# Main_MCU.net
KiCad netlist of a schematic drawn in Altium Designer
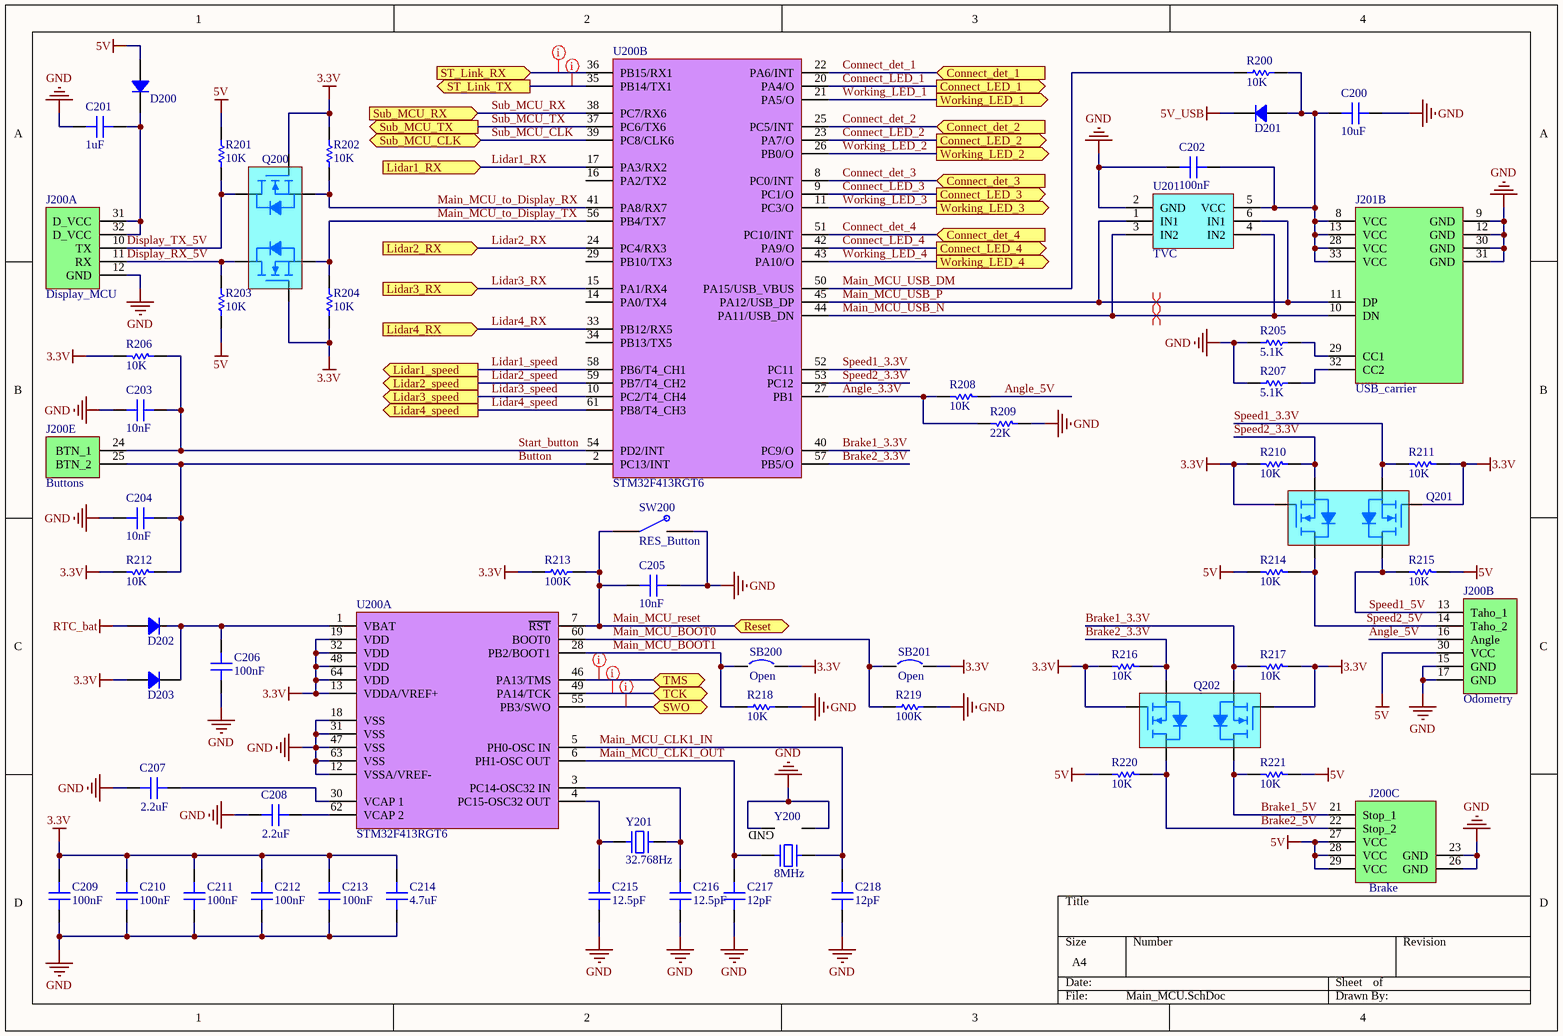
[diagram p0: Main_MCU.SchDoc]

(export (version "E")
  (design (tool "Eeschema 10.0.6"))
  (components
    (comp (ref "C200")
      (value "10uF")
      (footprint "CAP 0603")
      (description "SMT Capacitor")
      (libsource (lib "Schlib1") (part "Capacitor"))
    )
    (comp (ref "C201")
      (value "1uF")
      (footprint "CAP 0603")
      (description "SMT Capacitor")
      (libsource (lib "Schlib1") (part "Capacitor"))
    )
    (comp (ref "C202")
      (value "100nF")
      (footprint "CAP 0603")
      (description "SMT Capacitor")
      (libsource (lib "Schlib1") (part "Capacitor"))
    )
    (comp (ref "C203")
      (value "10nF")
      (footprint "CAP 0603")
      (description "SMT Capacitor")
      (libsource (lib "Schlib1") (part "Capacitor"))
    )
    (comp (ref "C204")
      (value "10nF")
      (footprint "CAP 0603")
      (description "SMT Capacitor")
      (libsource (lib "Schlib1") (part "Capacitor"))
    )
    (comp (ref "C205")
      (value "10nF")
      (footprint "CAP 0603")
      (description "SMT Capacitor")
      (libsource (lib "Schlib1") (part "Capacitor"))
    )
    (comp (ref "C206")
      (value "100nF")
      (footprint "CAP 0603")
      (description "SMT Capacitor")
      (libsource (lib "Schlib1") (part "Capacitor"))
    )
    (comp (ref "C207")
      (value "2.2uF")
      (footprint "CAP 0603")
      (description "SMT Capacitor")
      (libsource (lib "Schlib1") (part "Capacitor"))
    )
    (comp (ref "C208")
      (value "2.2uF")
      (footprint "CAP 0603")
      (description "SMT Capacitor")
      (libsource (lib "Schlib1") (part "Capacitor"))
    )
    (comp (ref "C209")
      (value "100nF")
      (footprint "CAP 0603")
      (description "SMT Capacitor")
      (libsource (lib "Schlib1") (part "Capacitor"))
    )
    (comp (ref "C210")
      (value "100nF")
      (footprint "CAP 0603")
      (description "SMT Capacitor")
      (libsource (lib "Schlib1") (part "Capacitor"))
    )
    (comp (ref "C211")
      (value "100nF")
      (footprint "CAP 0603")
      (description "SMT Capacitor")
      (libsource (lib "Schlib1") (part "Capacitor"))
    )
    (comp (ref "C212")
      (value "100nF")
      (footprint "CAP 0603")
      (description "SMT Capacitor")
      (libsource (lib "Schlib1") (part "Capacitor"))
    )
    (comp (ref "C213")
      (value "100nF")
      (footprint "CAP 0603")
      (description "SMT Capacitor")
      (libsource (lib "Schlib1") (part "Capacitor"))
    )
    (comp (ref "C214")
      (value "4.7uF")
      (footprint "CAP 1206")
      (description "SMT Capacitor")
      (libsource (lib "Schlib1") (part "Capacitor"))
    )
    (comp (ref "C215")
      (value "12.5pF")
      (footprint "CAP 0603")
      (description "SMT Capacitor")
      (libsource (lib "Schlib1") (part "Capacitor"))
    )
    (comp (ref "C216")
      (value "12.5pF")
      (footprint "CAP 0603")
      (description "SMT Capacitor")
      (libsource (lib "Schlib1") (part "Capacitor"))
    )
    (comp (ref "C217")
      (value "12pF")
      (footprint "CAP 0603")
      (description "SMT Capacitor")
      (libsource (lib "Schlib1") (part "Capacitor"))
    )
    (comp (ref "C218")
      (value "12pF")
      (footprint "CAP 0603")
      (description "SMT Capacitor")
      (libsource (lib "Schlib1") (part "Capacitor"))
    )
    (comp (ref "D200")
      (value "~")
      (footprint "Bourns DO214AC SMA - duplicate")
      (description "Rectifier Diode")
      (libsource (lib "Schlib1") (part "Diode"))
    )
    (comp (ref "D201")
      (value "~")
      (footprint "Bourns DO214AC SMA - duplicate")
      (description "Rectifier Diode")
      (libsource (lib "Schlib1") (part "Diode"))
    )
    (comp (ref "D202")
      (value "~")
      (footprint "SOD323HP")
      (description "Rectifier Diode")
      (libsource (lib "Schlib1") (part "Diode"))
    )
    (comp (ref "D203")
      (value "~")
      (footprint "SOD323HP")
      (description "Rectifier Diode")
      (libsource (lib "Schlib1") (part "Diode"))
    )
    (comp (ref "J200")
      (value "Display_MCU")
      (footprint "2167010409")
      (libsource (lib "Schlib1") (part "AUX_carrier"))
    )
    (comp (ref "J201")
      (value "USB_carrier")
      (footprint "2167010409")
      (libsource (lib "Schlib1") (part "USB_carrier"))
    )
    (comp (ref "Q200")
      (value "Double N mos")
      (footprint "TI SOT-563 DRL")
      (libsource (lib "") (part "Double N mos_1"))
    )
    (comp (ref "Q201")
      (value "Double N mos")
      (footprint "TI SOT-563 DRL")
      (libsource (lib "Schlib1") (part "Double N mos"))
    )
    (comp (ref "Q202")
      (value "Double N mos")
      (footprint "TI SOT-563 DRL")
      (libsource (lib "Schlib1") (part "Double N mos"))
    )
    (comp (ref "R200")
      (value "10K")
      (footprint "RES 0603")
      (description "Resistor")
      (fields (field (name "PUBLISHER") "Altium Limited"))
      (libsource (lib "Schlib1") (part "Res"))
    )
    (comp (ref "R201")
      (value "10K")
      (footprint "RES 0603")
      (description "Resistor")
      (fields (field (name "PUBLISHER") "Altium Limited"))
      (libsource (lib "Schlib1") (part "Res"))
    )
    (comp (ref "R202")
      (value "10K")
      (footprint "RES 0603")
      (description "Resistor")
      (fields (field (name "PUBLISHER") "Altium Limited"))
      (libsource (lib "Schlib1") (part "Res"))
    )
    (comp (ref "R203")
      (value "10K")
      (footprint "RES 0603")
      (description "Resistor")
      (fields (field (name "PUBLISHER") "Altium Limited"))
      (libsource (lib "Schlib1") (part "Res"))
    )
    (comp (ref "R204")
      (value "10K")
      (footprint "RES 0603")
      (description "Resistor")
      (fields (field (name "PUBLISHER") "Altium Limited"))
      (libsource (lib "Schlib1") (part "Res"))
    )
    (comp (ref "R205")
      (value "5.1K")
      (footprint "RES 0603")
      (description "Resistor")
      (fields (field (name "PUBLISHER") "Altium Limited"))
      (libsource (lib "Schlib1") (part "Res"))
    )
    (comp (ref "R206")
      (value "10K")
      (footprint "RES 0603")
      (description "Resistor")
      (fields (field (name "PUBLISHER") "Altium Limited"))
      (libsource (lib "Schlib1") (part "Res"))
    )
    (comp (ref "R207")
      (value "5.1K")
      (footprint "RES 0603")
      (description "Resistor")
      (fields (field (name "PUBLISHER") "Altium Limited"))
      (libsource (lib "Schlib1") (part "Res"))
    )
    (comp (ref "R208")
      (value "10K")
      (footprint "RES 0603")
      (description "Resistor")
      (fields (field (name "PUBLISHER") "Altium Limited"))
      (libsource (lib "Schlib1") (part "Res"))
    )
    (comp (ref "R209")
      (value "22K")
      (footprint "RES 0603")
      (description "Resistor")
      (fields (field (name "PUBLISHER") "Altium Limited"))
      (libsource (lib "Schlib1") (part "Res"))
    )
    (comp (ref "R210")
      (value "10K")
      (footprint "RES 0603")
      (description "Resistor")
      (fields (field (name "PUBLISHER") "Altium Limited"))
      (libsource (lib "Schlib1") (part "Res"))
    )
    (comp (ref "R211")
      (value "10K")
      (footprint "RES 0603")
      (description "Resistor")
      (fields (field (name "PUBLISHER") "Altium Limited"))
      (libsource (lib "Schlib1") (part "Res"))
    )
    (comp (ref "R212")
      (value "10K")
      (footprint "RES 0603")
      (description "Resistor")
      (fields (field (name "PUBLISHER") "Altium Limited"))
      (libsource (lib "Schlib1") (part "Res"))
    )
    (comp (ref "R213")
      (value "100K")
      (footprint "RES 0603")
      (description "Resistor")
      (fields (field (name "PUBLISHER") "Altium Limited"))
      (libsource (lib "Schlib1") (part "Res"))
    )
    (comp (ref "R214")
      (value "10K")
      (footprint "RES 0603")
      (description "Resistor")
      (fields (field (name "PUBLISHER") "Altium Limited"))
      (libsource (lib "Schlib1") (part "Res"))
    )
    (comp (ref "R215")
      (value "10K")
      (footprint "RES 0603")
      (description "Resistor")
      (fields (field (name "PUBLISHER") "Altium Limited"))
      (libsource (lib "Schlib1") (part "Res"))
    )
    (comp (ref "R216")
      (value "10K")
      (footprint "RES 0603")
      (description "Resistor")
      (fields (field (name "PUBLISHER") "Altium Limited"))
      (libsource (lib "Schlib1") (part "Res"))
    )
    (comp (ref "R217")
      (value "10K")
      (footprint "RES 0603")
      (description "Resistor")
      (fields (field (name "PUBLISHER") "Altium Limited"))
      (libsource (lib "Schlib1") (part "Res"))
    )
    (comp (ref "R218")
      (value "10K")
      (footprint "RES 0603")
      (description "Resistor")
      (fields (field (name "PUBLISHER") "Altium Limited"))
      (libsource (lib "Schlib1") (part "Res"))
    )
    (comp (ref "R219")
      (value "100K")
      (footprint "RES 0603")
      (description "Resistor")
      (fields (field (name "PUBLISHER") "Altium Limited"))
      (libsource (lib "Schlib1") (part "Res"))
    )
    (comp (ref "R220")
      (value "10K")
      (footprint "RES 0603")
      (description "Resistor")
      (fields (field (name "PUBLISHER") "Altium Limited"))
      (libsource (lib "Schlib1") (part "Res"))
    )
    (comp (ref "R221")
      (value "10K")
      (footprint "RES 0603")
      (description "Resistor")
      (fields (field (name "PUBLISHER") "Altium Limited"))
      (libsource (lib "Schlib1") (part "Res"))
    )
    (comp (ref "SB200")
      (value "Open")
      (footprint "SB_0603")
      (description "Circuit Breaker")
      (fields (field (name "PUBLISHER") "Altium Limited"))
      (libsource (lib "Schlib1") (part "Circuit Breaker"))
    )
    (comp (ref "SB201")
      (value "Open")
      (footprint "SB_0603")
      (description "Circuit Breaker")
      (fields (field (name "PUBLISHER") "Altium Limited"))
      (libsource (lib "Schlib1") (part "Circuit Breaker"))
    )
    (comp (ref "SW200")
      (value "RES_Button")
      (footprint "PTS636SM50JSMTRLFS")
      (libsource (lib "Schlib1") (part "RES_Button"))
    )
    (comp (ref "U200")
      (value "STM32F413RGT6")
      (footprint "QFP50P1200X1200X165-64N")
      (description "IC MCU 32BIT 1MB FLASH 64LQFP")
      (fields
        (field (name "MANUFACTURER") "STMicroelectronics")
        (field (name "OCTOPART") "https://octopart.com/stm32f413rgt6-stmicroelectronics-76512522")
      )
      (libsource (lib "Schlib1") (part "CMP-12105-000025-1"))
    )
    (comp (ref "U201")
      (value "TVC")
      (footprint "ECEN_1400:DIODES SOT-23-6 W6")
      (libsource (lib "Schlib1") (part "USB_TVC_protection"))
    )
    (comp (ref "Y200")
      (value "8MHz")
      (footprint "XTAL_ECS-80-10-33-CHN-TR3")
      (description "SMT Crystal")
      (libsource (lib "Schlib1") (part "Crystal 8Mhz"))
    )
    (comp (ref "Y201")
      (value "32.768Hz")
      (footprint "Crystal_32.768")
      (description "SMT Crystal")
      (libsource (lib "Schlib1") (part "Crystal_32.768Hz"))
    )
  )
  (nets
    (net (code "1") (name "/Angle_3.3V") (class "Default")
      (node (ref "R208") (pin "1") (pinfunction "1_1") (pintype "passive"))
      (node (ref "R209") (pin "1") (pinfunction "1_1") (pintype "passive"))
      (node (ref "U200") (pin "27") (pinfunction "PB1_27") (pintype "passive"))
    )
    (net (code "2") (name "/Angle_5V") (class "Default")
      (node (ref "J200") (pin "16") (pinfunction "Angle_16") (pintype "passive"))
      (node (ref "R208") (pin "2") (pinfunction "2_2") (pintype "passive"))
    )
    (net (code "3") (name "/Brake1_3.3V") (class "Default")
      (node (ref "Q202") (pin "5") (pinfunction "S1_5") (pintype "passive"))
      (node (ref "R217") (pin "1") (pinfunction "1_1") (pintype "passive"))
      (node (ref "U200") (pin "40") (pinfunction "PC9/O_40") (pintype "passive"))
    )
    (net (code "4") (name "/Brake1_5V") (class "Default")
      (node (ref "J200") (pin "21") (pinfunction "Stop_1_21") (pintype "passive"))
      (node (ref "Q202") (pin "3") (pinfunction "D1_3") (pintype "passive"))
      (node (ref "R221") (pin "1") (pinfunction "1_1") (pintype "passive"))
    )
    (net (code "5") (name "/Brake2_3.3V") (class "Default")
      (node (ref "Q202") (pin "2") (pinfunction "S2_2") (pintype "passive"))
      (node (ref "R216") (pin "2") (pinfunction "2_2") (pintype "passive"))
      (node (ref "U200") (pin "57") (pinfunction "PB5/O_57") (pintype "passive"))
    )
    (net (code "6") (name "/Brake2_5V") (class "Default")
      (node (ref "J200") (pin "22") (pinfunction "Stop_2_22") (pintype "passive"))
      (node (ref "Q202") (pin "6") (pinfunction "D2_6") (pintype "passive"))
      (node (ref "R220") (pin "2") (pinfunction "2_2") (pintype "passive"))
    )
    (net (code "7") (name "/Button") (class "Default")
      (node (ref "C204") (pin "1") (pinfunction "1_1") (pintype "passive"))
      (node (ref "J200") (pin "25") (pinfunction "BTN_2_25") (pintype "passive"))
      (node (ref "R212") (pin "2") (pinfunction "2_2") (pintype "passive"))
      (node (ref "U200") (pin "2") (pinfunction "PC13/INT_2") (pintype "passive"))
    )
    (net (code "8") (name "/Connect_LED_1") (class "Default")
      (node (ref "U200") (pin "20") (pinfunction "PA4/O_20") (pintype "passive"))
    )
    (net (code "9") (name "/Connect_LED_2") (class "Default")
      (node (ref "U200") (pin "23") (pinfunction "PA7/O_23") (pintype "passive"))
    )
    (net (code "10") (name "/Connect_LED_3") (class "Default")
      (node (ref "U200") (pin "9") (pinfunction "PC1/O_9") (pintype "passive"))
    )
    (net (code "11") (name "/Connect_LED_4") (class "Default")
      (node (ref "U200") (pin "42") (pinfunction "PA9/O_42") (pintype "passive"))
    )
    (net (code "12") (name "/Connect_det_1") (class "Default")
      (node (ref "U200") (pin "22") (pinfunction "PA6/INT_22") (pintype "passive"))
    )
    (net (code "13") (name "/Connect_det_2") (class "Default")
      (node (ref "U200") (pin "25") (pinfunction "PC5/INT_25") (pintype "passive"))
    )
    (net (code "14") (name "/Connect_det_3") (class "Default")
      (node (ref "U200") (pin "8") (pinfunction "PC0/INT_8") (pintype "passive"))
    )
    (net (code "15") (name "/Connect_det_4") (class "Default")
      (node (ref "U200") (pin "51") (pinfunction "PC10/INT_51") (pintype "passive"))
    )
    (net (code "16") (name "/Display_RX_5V") (class "Default")
      (node (ref "J200") (pin "11") (pinfunction "RX_11") (pintype "passive"))
      (node (ref "Q200") (pin "3") (pinfunction "D1_3") (pintype "passive"))
      (node (ref "R203") (pin "2") (pinfunction "2_2") (pintype "passive"))
    )
    (net (code "17") (name "/Display_TX_5V") (class "Default")
      (node (ref "J200") (pin "10") (pinfunction "TX_10") (pintype "passive"))
      (node (ref "Q200") (pin "6") (pinfunction "D2_6") (pintype "passive"))
      (node (ref "R201") (pin "1") (pinfunction "1_1") (pintype "passive"))
    )
    (net (code "18") (name "/Lidar1_RX") (class "Default")
      (node (ref "U200") (pin "17") (pinfunction "PA3/RX2_17") (pintype "passive"))
    )
    (net (code "19") (name "/Lidar1_speed") (class "Default")
      (node (ref "U200") (pin "58") (pinfunction "PB6/T4_CH1_58") (pintype "passive"))
    )
    (net (code "20") (name "/Lidar2_RX") (class "Default")
      (node (ref "U200") (pin "24") (pinfunction "PC4/RX3_24") (pintype "passive"))
    )
    (net (code "21") (name "/Lidar2_speed") (class "Default")
      (node (ref "U200") (pin "59") (pinfunction "PB7/T4_CH2_59") (pintype "passive"))
    )
    (net (code "22") (name "/Lidar3_RX") (class "Default")
      (node (ref "U200") (pin "15") (pinfunction "PA1/RX4_15") (pintype "passive"))
    )
    (net (code "23") (name "/Lidar3_speed") (class "Default")
      (node (ref "U200") (pin "10") (pinfunction "PC2/T4_CH4_10") (pintype "passive"))
    )
    (net (code "24") (name "/Lidar4_RX") (class "Default")
      (node (ref "U200") (pin "33") (pinfunction "PB12/RX5_33") (pintype "passive"))
    )
    (net (code "25") (name "/Lidar4_speed") (class "Default")
      (node (ref "U200") (pin "61") (pinfunction "PB8/T4_CH3_61") (pintype "passive"))
    )
    (net (code "26") (name "/Main_MCU_BOOT0") (class "Default")
      (node (ref "R219") (pin "2") (pinfunction "2_2") (pintype "passive"))
      (node (ref "SB201") (pin "1") (pinfunction "1_1") (pintype "passive"))
      (node (ref "U200") (pin "60") (pinfunction "BOOT0_60") (pintype "passive"))
    )
    (net (code "27") (name "/Main_MCU_BOOT1") (class "Default")
      (node (ref "R218") (pin "2") (pinfunction "2_2") (pintype "passive"))
      (node (ref "SB200") (pin "1") (pinfunction "1_1") (pintype "passive"))
      (node (ref "U200") (pin "28") (pinfunction "PB2/BOOT1_28") (pintype "passive"))
    )
    (net (code "28") (name "/Main_MCU_CLK1_IN") (class "Default")
      (node (ref "C218") (pin "2") (pinfunction "2_2") (pintype "passive"))
      (node (ref "U200") (pin "5") (pinfunction "PH0-OSC_IN_5") (pintype "passive"))
      (node (ref "Y200") (pin "3") (pinfunction "3_3") (pintype "passive"))
    )
    (net (code "29") (name "/Main_MCU_CLK1_OUT") (class "Default")
      (node (ref "C217") (pin "2") (pinfunction "2_2") (pintype "passive"))
      (node (ref "U200") (pin "6") (pinfunction "PH1-OSC_OUT_6") (pintype "passive"))
      (node (ref "Y200") (pin "1") (pinfunction "1_1") (pintype "passive"))
    )
    (net (code "30") (name "/Main_MCU_USB_DM") (class "Default")
      (node (ref "R200") (pin "2") (pinfunction "2_2") (pintype "passive"))
      (node (ref "U200") (pin "50") (pinfunction "PA15/USB_VBUS_50") (pintype "passive"))
    )
    (net (code "31") (name "/Main_MCU_USB_N") (class "Default")
      (node (ref "J201") (pin "10") (pinfunction "DN_10") (pintype "passive"))
      (node (ref "U200") (pin "44") (pinfunction "PA11/USB_DN_44") (pintype "passive"))
      (node (ref "U201") (pin "3") (pinfunction "IN2_3") (pintype "passive"))
      (node (ref "U201") (pin "4") (pinfunction "IN2_4") (pintype "passive"))
    )
    (net (code "32") (name "/Main_MCU_USB_P") (class "Default")
      (node (ref "J201") (pin "11") (pinfunction "DP_11") (pintype "passive"))
      (node (ref "U200") (pin "45") (pinfunction "PA12/USB_DP_45") (pintype "passive"))
      (node (ref "U201") (pin "1") (pinfunction "IN1_1") (pintype "passive"))
      (node (ref "U201") (pin "6") (pinfunction "IN1_6") (pintype "passive"))
    )
    (net (code "33") (name "/Main_MCU_reset") (class "Default")
      (node (ref "C205") (pin "1") (pinfunction "1_1") (pintype "passive"))
      (node (ref "R213") (pin "1") (pinfunction "1_1") (pintype "passive"))
      (node (ref "SW200") (pin "1") (pinfunction "1_1") (pintype "passive"))
      (node (ref "U200") (pin "7") (pinfunction "~{RST}_7") (pintype "passive"))
    )
    (net (code "34") (name "/Main_MCU_to_Display_RX") (class "Default")
      (node (ref "Q200") (pin "2") (pinfunction "S2_2") (pintype "passive"))
      (node (ref "R202") (pin "1") (pinfunction "1_1") (pintype "passive"))
      (node (ref "U200") (pin "41") (pinfunction "PA8/RX7_41") (pintype "passive"))
    )
    (net (code "35") (name "/Main_MCU_to_Display_TX") (class "Default")
      (node (ref "Q200") (pin "5") (pinfunction "S1_5") (pintype "passive"))
      (node (ref "R204") (pin "2") (pinfunction "2_2") (pintype "passive"))
      (node (ref "U200") (pin "56") (pinfunction "PB4/TX7_56") (pintype "passive"))
    )
    (net (code "36") (name "/ST_Link_RX") (class "Default")
      (node (ref "U200") (pin "36") (pinfunction "PB15/RX1_36") (pintype "passive"))
    )
    (net (code "37") (name "/ST_Link_TX") (class "Default")
      (node (ref "U200") (pin "35") (pinfunction "PB14/TX1_35") (pintype "passive"))
    )
    (net (code "38") (name "/SWO") (class "Default")
      (node (ref "U200") (pin "55") (pinfunction "PB3/SWO_55") (pintype "passive"))
    )
    (net (code "39") (name "/Speed1_3.3V") (class "Default")
      (node (ref "Q201") (pin "5") (pinfunction "S1_5") (pintype "passive"))
      (node (ref "R211") (pin "1") (pinfunction "1_1") (pintype "passive"))
      (node (ref "U200") (pin "52") (pinfunction "PC11_52") (pintype "passive"))
    )
    (net (code "40") (name "/Speed1_5V") (class "Default")
      (node (ref "J200") (pin "13") (pinfunction "Taho_1_13") (pintype "passive"))
      (node (ref "Q201") (pin "3") (pinfunction "D1_3") (pintype "passive"))
      (node (ref "R215") (pin "1") (pinfunction "1_1") (pintype "passive"))
    )
    (net (code "41") (name "/Speed2_3.3V") (class "Default")
      (node (ref "Q201") (pin "2") (pinfunction "S2_2") (pintype "passive"))
      (node (ref "R210") (pin "2") (pinfunction "2_2") (pintype "passive"))
      (node (ref "U200") (pin "53") (pinfunction "PC12_53") (pintype "passive"))
    )
    (net (code "42") (name "/Speed2_5V") (class "Default")
      (node (ref "J200") (pin "14") (pinfunction "Taho_2_14") (pintype "passive"))
      (node (ref "Q201") (pin "6") (pinfunction "D2_6") (pintype "passive"))
      (node (ref "R214") (pin "2") (pinfunction "2_2") (pintype "passive"))
    )
    (net (code "43") (name "/Start_button") (class "Default")
      (node (ref "C203") (pin "1") (pinfunction "1_1") (pintype "passive"))
      (node (ref "J200") (pin "24") (pinfunction "BTN_1_24") (pintype "passive"))
      (node (ref "R206") (pin "2") (pinfunction "2_2") (pintype "passive"))
      (node (ref "U200") (pin "54") (pinfunction "PD2/INT_54") (pintype "passive"))
    )
    (net (code "44") (name "/Sub_MCU_CLK") (class "Default")
      (node (ref "U200") (pin "39") (pinfunction "PC8/CLK6_39") (pintype "passive"))
    )
    (net (code "45") (name "/Sub_MCU_RX") (class "Default")
      (node (ref "U200") (pin "38") (pinfunction "PC7/RX6_38") (pintype "passive"))
    )
    (net (code "46") (name "/Sub_MCU_TX") (class "Default")
      (node (ref "U200") (pin "37") (pinfunction "PC6/TX6_37") (pintype "passive"))
    )
    (net (code "47") (name "/TCK") (class "Default")
      (node (ref "U200") (pin "49") (pinfunction "PA14/TCK_49") (pintype "passive"))
    )
    (net (code "48") (name "/TMS") (class "Default")
      (node (ref "U200") (pin "46") (pinfunction "PA13/TMS_46") (pintype "passive"))
    )
    (net (code "49") (name "/Working_LED_1") (class "Default")
      (node (ref "U200") (pin "21") (pinfunction "PA5/O_21") (pintype "passive"))
    )
    (net (code "50") (name "/Working_LED_2") (class "Default")
      (node (ref "U200") (pin "26") (pinfunction "PB0/O_26") (pintype "passive"))
    )
    (net (code "51") (name "/Working_LED_3") (class "Default")
      (node (ref "U200") (pin "11") (pinfunction "PC3/O_11") (pintype "passive"))
    )
    (net (code "52") (name "/Working_LED_4") (class "Default")
      (node (ref "U200") (pin "43") (pinfunction "PA10/O_43") (pintype "passive"))
    )
    (net (code "53") (name "3.3V") (class "Default")
      (node (ref "C209") (pin "2") (pinfunction "2_2") (pintype "passive"))
      (node (ref "C210") (pin "2") (pinfunction "2_2") (pintype "passive"))
      (node (ref "C211") (pin "2") (pinfunction "2_2") (pintype "passive"))
      (node (ref "C212") (pin "2") (pinfunction "2_2") (pintype "passive"))
      (node (ref "C213") (pin "2") (pinfunction "2_2") (pintype "passive"))
      (node (ref "C214") (pin "2") (pinfunction "2_2") (pintype "passive"))
      (node (ref "D203") (pin "1") (pinfunction "1_1") (pintype "passive"))
      (node (ref "Q200") (pin "1") (pinfunction "G2_1") (pintype "passive"))
      (node (ref "Q200") (pin "4") (pinfunction "G1_4") (pintype "passive"))
      (node (ref "Q201") (pin "1") (pinfunction "G2_1") (pintype "passive"))
      (node (ref "Q201") (pin "4") (pinfunction "G1_4") (pintype "passive"))
      (node (ref "Q202") (pin "1") (pinfunction "G2_1") (pintype "passive"))
      (node (ref "Q202") (pin "4") (pinfunction "G1_4") (pintype "passive"))
      (node (ref "R202") (pin "2") (pinfunction "2_2") (pintype "passive"))
      (node (ref "R204") (pin "1") (pinfunction "1_1") (pintype "passive"))
      (node (ref "R206") (pin "1") (pinfunction "1_1") (pintype "passive"))
      (node (ref "R210") (pin "1") (pinfunction "1_1") (pintype "passive"))
      (node (ref "R211") (pin "2") (pinfunction "2_2") (pintype "passive"))
      (node (ref "R212") (pin "1") (pinfunction "1_1") (pintype "passive"))
      (node (ref "R213") (pin "2") (pinfunction "2_2") (pintype "passive"))
      (node (ref "R216") (pin "1") (pinfunction "1_1") (pintype "passive"))
      (node (ref "R217") (pin "2") (pinfunction "2_2") (pintype "passive"))
      (node (ref "SB200") (pin "2") (pinfunction "2_2") (pintype "passive"))
      (node (ref "SB201") (pin "2") (pinfunction "2_2") (pintype "passive"))
      (node (ref "U200") (pin "13") (pinfunction "VDDA/VREF+_13") (pintype "power_in"))
      (node (ref "U200") (pin "19") (pinfunction "VDD_19") (pintype "power_in"))
      (node (ref "U200") (pin "32") (pinfunction "VDD_32") (pintype "power_in"))
      (node (ref "U200") (pin "48") (pinfunction "VDD_48") (pintype "power_in"))
      (node (ref "U200") (pin "64") (pinfunction "VDD_64") (pintype "power_in"))
    )
    (net (code "54") (name "5V") (class "Default")
      (node (ref "D200") (pin "1") (pinfunction "1_1") (pintype "passive"))
      (node (ref "J200") (pin "27") (pinfunction "VCC_27") (pintype "passive"))
      (node (ref "J200") (pin "28") (pinfunction "VCC_28") (pintype "passive"))
      (node (ref "J200") (pin "29") (pinfunction "VCC_29") (pintype "passive"))
      (node (ref "J200") (pin "30") (pinfunction "VCC_30") (pintype "passive"))
      (node (ref "R201") (pin "2") (pinfunction "2_2") (pintype "passive"))
      (node (ref "R203") (pin "1") (pinfunction "1_1") (pintype "passive"))
      (node (ref "R214") (pin "1") (pinfunction "1_1") (pintype "passive"))
      (node (ref "R215") (pin "2") (pinfunction "2_2") (pintype "passive"))
      (node (ref "R220") (pin "1") (pinfunction "1_1") (pintype "passive"))
      (node (ref "R221") (pin "2") (pinfunction "2_2") (pintype "passive"))
    )
    (net (code "55") (name "5V_USB") (class "Default")
      (node (ref "D201") (pin "2") (pinfunction "2_2") (pintype "passive"))
    )
    (net (code "56") (name "GND") (class "Default")
      (node (ref "C200") (pin "2") (pinfunction "2_2") (pintype "passive"))
      (node (ref "C201") (pin "1") (pinfunction "1_1") (pintype "passive"))
      (node (ref "C202") (pin "1") (pinfunction "1_1") (pintype "passive"))
      (node (ref "C203") (pin "2") (pinfunction "2_2") (pintype "passive"))
      (node (ref "C204") (pin "2") (pinfunction "2_2") (pintype "passive"))
      (node (ref "C205") (pin "2") (pinfunction "2_2") (pintype "passive"))
      (node (ref "C206") (pin "1") (pinfunction "1_1") (pintype "passive"))
      (node (ref "C207") (pin "2") (pinfunction "2_2") (pintype "passive"))
      (node (ref "C208") (pin "2") (pinfunction "2_2") (pintype "passive"))
      (node (ref "C209") (pin "1") (pinfunction "1_1") (pintype "passive"))
      (node (ref "C210") (pin "1") (pinfunction "1_1") (pintype "passive"))
      (node (ref "C211") (pin "1") (pinfunction "1_1") (pintype "passive"))
      (node (ref "C212") (pin "1") (pinfunction "1_1") (pintype "passive"))
      (node (ref "C213") (pin "1") (pinfunction "1_1") (pintype "passive"))
      (node (ref "C214") (pin "1") (pinfunction "1_1") (pintype "passive"))
      (node (ref "C215") (pin "1") (pinfunction "1_1") (pintype "passive"))
      (node (ref "C216") (pin "1") (pinfunction "1_1") (pintype "passive"))
      (node (ref "C217") (pin "1") (pinfunction "1_1") (pintype "passive"))
      (node (ref "C218") (pin "1") (pinfunction "1_1") (pintype "passive"))
      (node (ref "J200") (pin "12") (pinfunction "GND_12") (pintype "passive"))
      (node (ref "J200") (pin "15") (pinfunction "GND_15") (pintype "passive"))
      (node (ref "J200") (pin "17") (pinfunction "GND_17") (pintype "passive"))
      (node (ref "J200") (pin "23") (pinfunction "GND_23") (pintype "passive"))
      (node (ref "J200") (pin "26") (pinfunction "GND_26") (pintype "passive"))
      (node (ref "J201") (pin "12") (pinfunction "GND_12") (pintype "passive"))
      (node (ref "J201") (pin "30") (pinfunction "GND_30") (pintype "passive"))
      (node (ref "J201") (pin "31") (pinfunction "GND_31") (pintype "passive"))
      (node (ref "J201") (pin "9") (pinfunction "GND_9") (pintype "passive"))
      (node (ref "R205") (pin "1") (pinfunction "1_1") (pintype "passive"))
      (node (ref "R207") (pin "1") (pinfunction "1_1") (pintype "passive"))
      (node (ref "R209") (pin "2") (pinfunction "2_2") (pintype "passive"))
      (node (ref "R218") (pin "1") (pinfunction "1_1") (pintype "passive"))
      (node (ref "R219") (pin "1") (pinfunction "1_1") (pintype "passive"))
      (node (ref "SW200") (pin "2") (pinfunction "2_2") (pintype "passive"))
      (node (ref "U200") (pin "12") (pinfunction "VSSA/VREF-_12") (pintype "power_in"))
      (node (ref "U200") (pin "18") (pinfunction "VSS_18") (pintype "power_in"))
      (node (ref "U200") (pin "31") (pinfunction "VSS_31") (pintype "power_in"))
      (node (ref "U200") (pin "47") (pinfunction "VSS_47") (pintype "power_in"))
      (node (ref "U200") (pin "63") (pinfunction "VSS_63") (pintype "power_in"))
      (node (ref "U201") (pin "2") (pinfunction "GND_2") (pintype "passive"))
      (node (ref "Y200") (pin "2") (pinfunction "GND_2") (pintype "passive"))
      (node (ref "Y200") (pin "4") (pinfunction "GND_4") (pintype "passive"))
    )
    (net (code "57") (name "Net-(C201-Pad2)") (class "Default")
      (node (ref "C201") (pin "2") (pinfunction "2_2") (pintype "passive"))
      (node (ref "D200") (pin "2") (pinfunction "2_2") (pintype "passive"))
      (node (ref "J200") (pin "31") (pinfunction "D_VCC_31") (pintype "passive"))
      (node (ref "J200") (pin "32") (pinfunction "D_VCC_32") (pintype "passive"))
    )
    (net (code "58") (name "Net-(J201B-CC1)") (class "Default")
      (node (ref "J201") (pin "29") (pinfunction "CC1_29") (pintype "passive"))
      (node (ref "R205") (pin "2") (pinfunction "2_2") (pintype "passive"))
    )
    (net (code "59") (name "Net-(J201B-CC2)") (class "Default")
      (node (ref "J201") (pin "32") (pinfunction "CC2_32") (pintype "passive"))
      (node (ref "R207") (pin "2") (pinfunction "2_2") (pintype "passive"))
    )
    (net (code "60") (name "Net-(U200A-PC14-OSC32_IN)") (class "Default")
      (node (ref "C216") (pin "2") (pinfunction "2_2") (pintype "passive"))
      (node (ref "U200") (pin "3") (pinfunction "PC14-OSC32_IN_3") (pintype "passive"))
      (node (ref "Y201") (pin "2") (pinfunction "2_2") (pintype "passive"))
    )
    (net (code "61") (name "Net-(U200A-PC15-OSC32_OUT)") (class "Default")
      (node (ref "C215") (pin "2") (pinfunction "2_2") (pintype "passive"))
      (node (ref "U200") (pin "4") (pinfunction "PC15-OSC32_OUT_4") (pintype "passive"))
      (node (ref "Y201") (pin "1") (pinfunction "1_1") (pintype "passive"))
    )
    (net (code "62") (name "Net-(U200A-VBAT)") (class "Default")
      (node (ref "C206") (pin "2") (pinfunction "2_2") (pintype "passive"))
      (node (ref "D202") (pin "2") (pinfunction "2_2") (pintype "passive"))
      (node (ref "D203") (pin "2") (pinfunction "2_2") (pintype "passive"))
      (node (ref "U200") (pin "1") (pinfunction "VBAT_1") (pintype "power_in"))
    )
    (net (code "63") (name "Net-(U200A-VCAP_1)") (class "Default")
      (node (ref "C207") (pin "1") (pinfunction "1_1") (pintype "passive"))
      (node (ref "U200") (pin "30") (pinfunction "VCAP_1_30") (pintype "power_in"))
    )
    (net (code "64") (name "Net-(U200A-VCAP_2)") (class "Default")
      (node (ref "C208") (pin "1") (pinfunction "1_1") (pintype "passive"))
      (node (ref "U200") (pin "62") (pinfunction "VCAP_2_62") (pintype "power_in"))
    )
    (net (code "65") (name "Net-(U201-VCC)") (class "Default")
      (node (ref "C200") (pin "1") (pinfunction "1_1") (pintype "passive"))
      (node (ref "C202") (pin "2") (pinfunction "2_2") (pintype "passive"))
      (node (ref "D201") (pin "1") (pinfunction "1_1") (pintype "passive"))
      (node (ref "J201") (pin "13") (pinfunction "VCC_13") (pintype "passive"))
      (node (ref "J201") (pin "28") (pinfunction "VCC_28") (pintype "passive"))
      (node (ref "J201") (pin "33") (pinfunction "VCC_33") (pintype "passive"))
      (node (ref "J201") (pin "8") (pinfunction "VCC_8") (pintype "passive"))
      (node (ref "R200") (pin "1") (pinfunction "1_1") (pintype "passive"))
      (node (ref "U201") (pin "5") (pinfunction "VCC_5") (pintype "passive"))
    )
    (net (code "66") (name "RTC_bat") (class "Default")
      (node (ref "D202") (pin "1") (pinfunction "1_1") (pintype "passive"))
    )
    (net (code "67") (name "unconnected-(U200B-PA0{slash}TX4-Pad14)") (class "Default")
      (node (ref "U200") (pin "14") (pinfunction "PA0/TX4_14") (pintype "passive"))
    )
    (net (code "68") (name "unconnected-(U200B-PA2{slash}TX2-Pad16)") (class "Default")
      (node (ref "U200") (pin "16") (pinfunction "PA2/TX2_16") (pintype "passive"))
    )
    (net (code "69") (name "unconnected-(U200B-PB10{slash}TX3-Pad29)") (class "Default")
      (node (ref "U200") (pin "29") (pinfunction "PB10/TX3_29") (pintype "passive"))
    )
    (net (code "70") (name "unconnected-(U200B-PB13{slash}TX5-Pad34)") (class "Default")
      (node (ref "U200") (pin "34") (pinfunction "PB13/TX5_34") (pintype "passive"))
    )
  )
)
